# ESP_ILI9341_V3.net
KiCad netlist of a schematic drawn in EAGLE
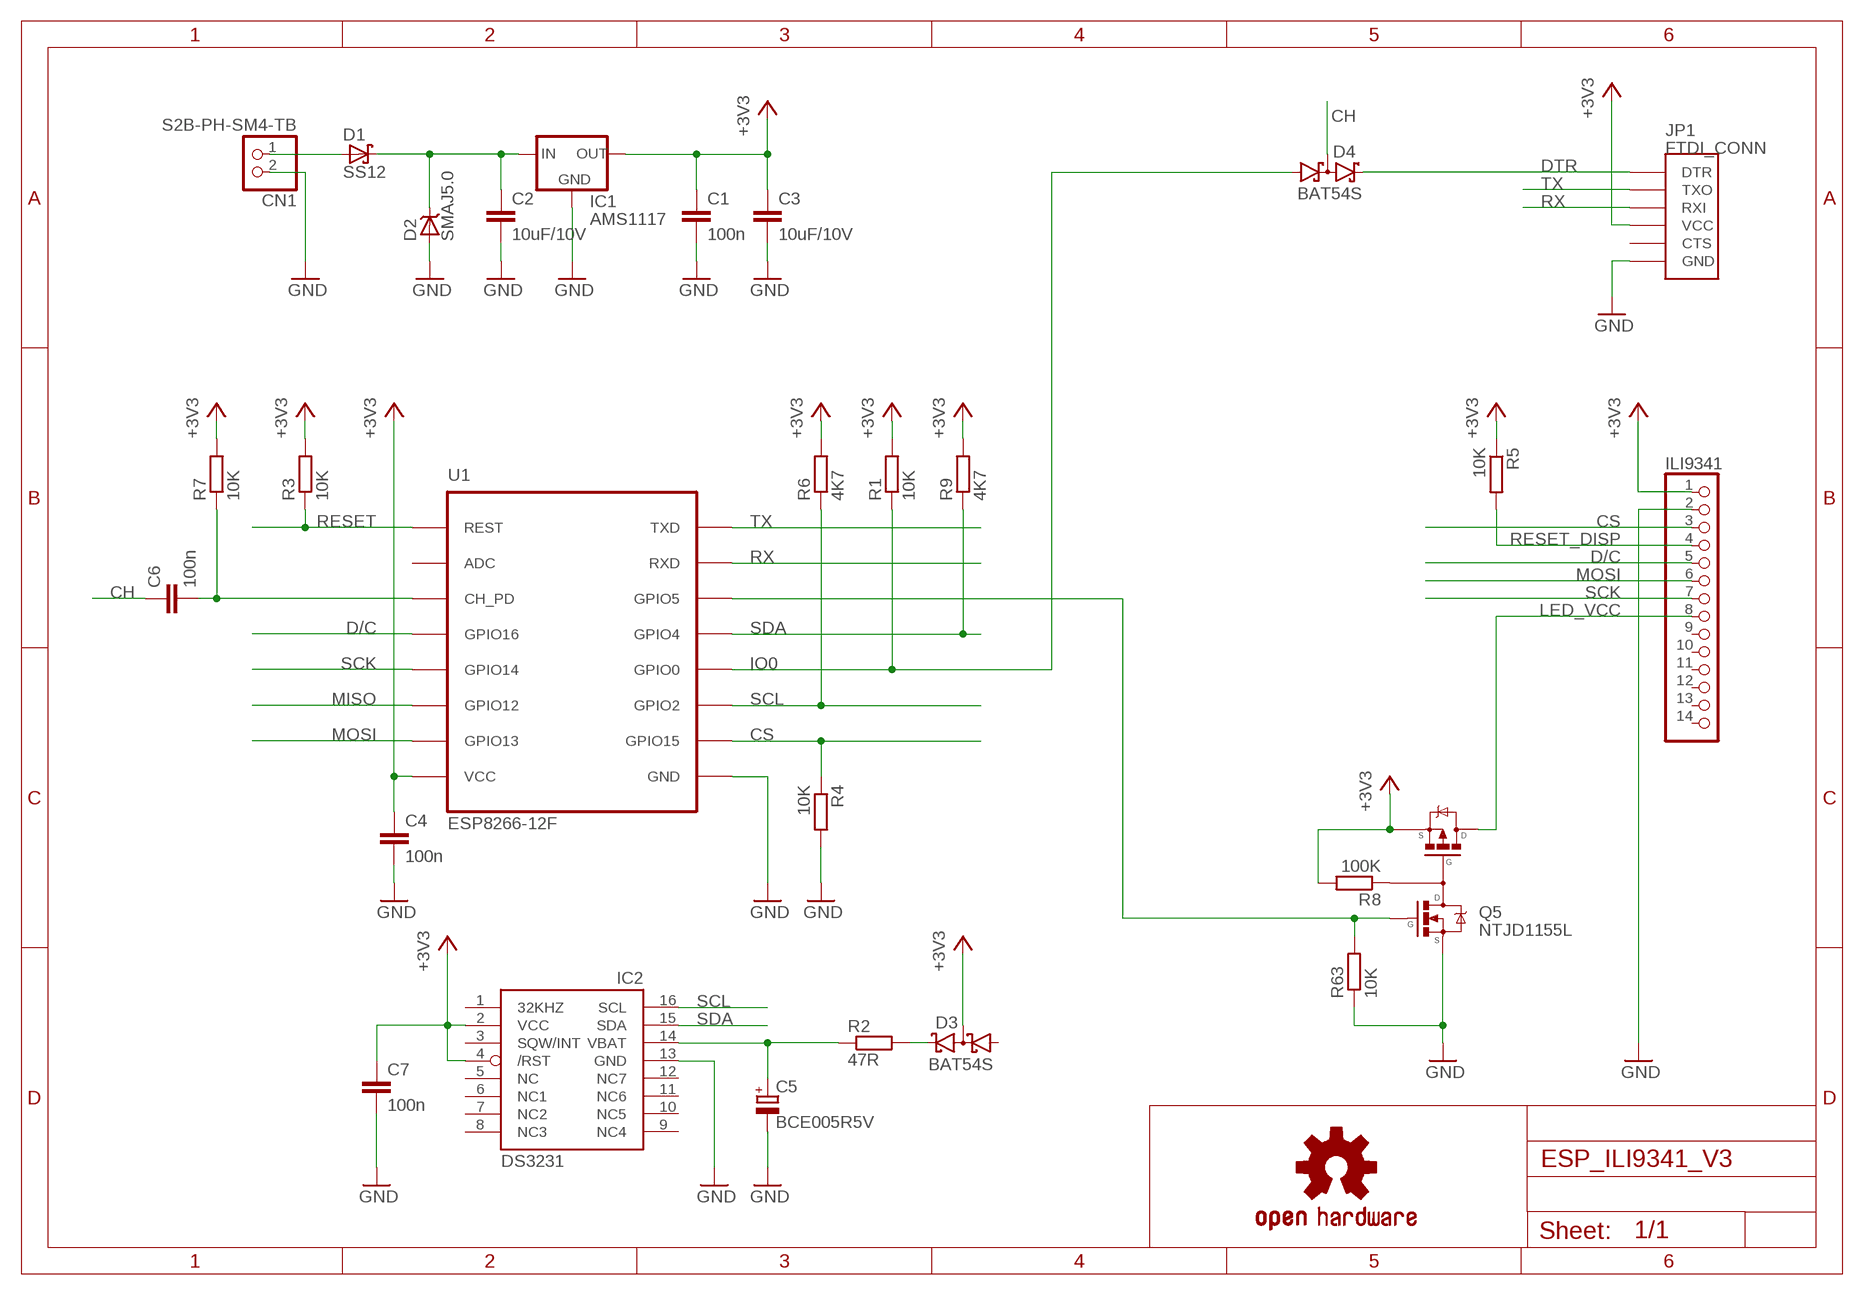
[diagram p0: schematic, sheet 1]

(export (version "E")
  (design (tool "Eeschema 10.0.6"))
  (components
    (comp (ref "C1")
      (value "100n")
      (footprint "eagle-import:C0805")
      (libsource (lib "eagle-import") (part "C-EUC0805"))
    )
    (comp (ref "C2")
      (value "10uF/10V")
      (footprint "eagle-import:C0805")
      (libsource (lib "eagle-import") (part "C-EUC0805"))
    )
    (comp (ref "C3")
      (value "10uF/10V")
      (footprint "eagle-import:C0805")
      (libsource (lib "eagle-import") (part "C-EUC0805"))
    )
    (comp (ref "C4")
      (value "100n")
      (footprint "eagle-import:C0805")
      (libsource (lib "eagle-import") (part "C-EUC0805"))
    )
    (comp (ref "C5")
      (value "BCE005R5V")
      (footprint "eagle-import:BCE")
      (libsource (lib "eagle-import") (part "BCE?V005R5"))
    )
    (comp (ref "C6")
      (value "100n")
      (footprint "eagle-import:C0805")
      (libsource (lib "eagle-import") (part "C-EUC0805"))
    )
    (comp (ref "C7")
      (value "100n")
      (footprint "eagle-import:C0805")
      (libsource (lib "eagle-import") (part "C-EUC0805"))
    )
    (comp (ref "CN1")
      (value "S2B-PH-SM4-TB")
      (footprint "eagle-import:JST-PH-2-SMT-RA")
      (libsource (lib "eagle-import") (part "JST_2PIN-SMT-RA"))
    )
    (comp (ref "D1")
      (value "SS12")
      (footprint "eagle-import:DO214AC")
      (libsource (lib "eagle-import") (part "SS?12"))
    )
    (comp (ref "D2")
      (value "SMAJ5.0")
      (footprint "eagle-import:DO214AC")
      (libsource (lib "eagle-import") (part "SM?JA5.0"))
    )
    (comp (ref "D3")
      (value "BAT54S")
      (footprint "eagle-import:SOT23")
      (libsource (lib "eagle-import") (part "BAT54S"))
    )
    (comp (ref "D4")
      (value "BAT54S")
      (footprint "eagle-import:SOT23")
      (libsource (lib "eagle-import") (part "BAT54S"))
    )
    (comp (ref "IC1")
      (value "AMS1117")
      (footprint "eagle-import:SOT223")
      (libsource (lib "eagle-import") (part "LM1117-3.3"))
    )
    (comp (ref "IC2")
      (value "DS3231/SO")
      (footprint "eagle-import:SO16W")
      (libsource (lib "eagle-import") (part "DS3231/SO"))
    )
    (comp (ref "ILI9341")
      (value "PINHD-1X14")
      (footprint "eagle-import:1X14")
      (libsource (lib "eagle-import") (part "PINHD-1X14"))
    )
    (comp (ref "JP1")
      (value "FTDI_CONN")
      (footprint "eagle-import:FTDI")
      (libsource (lib "eagle-import") (part "FTDI_CONN"))
    )
    (comp (ref "LOGO1")
      (value "OSHW-LOGOM-COPPER")
      (footprint "eagle-import:OSHW-LOGO-M_COPPER")
      (libsource (lib "eagle-import") (part "OSHW-LOGOM-COPPER"))
    )
    (comp (ref "Q5")
      (value "NTJD1155L")
      (footprint "eagle-import:SOT363")
      (libsource (lib "eagle-import") (part "NTJD1155L"))
    )
    (comp (ref "R1")
      (value "10K")
      (footprint "eagle-import:R0805")
      (libsource (lib "eagle-import") (part "R-EU_R0805"))
    )
    (comp (ref "R2")
      (value "47R")
      (footprint "eagle-import:R1206")
      (libsource (lib "eagle-import") (part "rcl_334_R-EU_R1206"))
    )
    (comp (ref "R3")
      (value "10K")
      (footprint "eagle-import:R0805")
      (libsource (lib "eagle-import") (part "R-EU_R0805"))
    )
    (comp (ref "R4")
      (value "10K")
      (footprint "eagle-import:R0805")
      (libsource (lib "eagle-import") (part "R-EU_R0805"))
    )
    (comp (ref "R5")
      (value "10K")
      (footprint "eagle-import:R0805")
      (libsource (lib "eagle-import") (part "R-EU_R0805"))
    )
    (comp (ref "R6")
      (value "4K7")
      (footprint "eagle-import:R0805")
      (libsource (lib "eagle-import") (part "R-EU_R0805"))
    )
    (comp (ref "R7")
      (value "10K")
      (footprint "eagle-import:R0805")
      (libsource (lib "eagle-import") (part "R-EU_R0805"))
    )
    (comp (ref "R8")
      (value "100K")
      (footprint "eagle-import:R0805")
      (libsource (lib "eagle-import") (part "R-EU_R0805"))
    )
    (comp (ref "R9")
      (value "4K7")
      (footprint "eagle-import:R0805")
      (libsource (lib "eagle-import") (part "R-EU_R0805"))
    )
    (comp (ref "R63")
      (value "10K")
      (footprint "eagle-import:R0805")
      (libsource (lib "eagle-import") (part "rcl_334_R-EU_R0805"))
    )
    (comp (ref "U1")
      (value "ESP8266-12F")
      (footprint "eagle-import:ESP-12")
      (libsource (lib "eagle-import") (part "ESP8266-12S"))
    )
  )
  (nets
    (net (code "1") (name "+3V3") (class "Default")
      (node (ref "C1") (pin "1") (pinfunction "1_1") (pintype "passive"))
      (node (ref "C3") (pin "1") (pinfunction "1_1") (pintype "passive"))
      (node (ref "C4") (pin "1") (pinfunction "1_1") (pintype "passive"))
      (node (ref "C7") (pin "1") (pinfunction "1_1") (pintype "passive"))
      (node (ref "D3") (pin "3") (pinfunction "C1A2_3") (pintype "passive"))
      (node (ref "IC1") (pin "2") (pinfunction "OUT_2") (pintype "output"))
      (node (ref "IC1") (pin "4") (pinfunction "OUT_4") (pintype "output"))
      (node (ref "IC2") (pin "2") (pinfunction "VCC_2") (pintype "power_in"))
      (node (ref "IC2") (pin "4") (pinfunction "/RST_4") (pintype "passive"))
      (node (ref "ILI9341") (pin "1") (pinfunction "1_1") (pintype "passive"))
      (node (ref "JP1") (pin "P$4") (pinfunction "VCC_P$4") (pintype "bidirectional"))
      (node (ref "Q5") (pin "4") (pinfunction "S2_4") (pintype "passive"))
      (node (ref "R1") (pin "2") (pinfunction "2_2") (pintype "passive"))
      (node (ref "R3") (pin "2") (pinfunction "2_2") (pintype "passive"))
      (node (ref "R5") (pin "1") (pinfunction "1_1") (pintype "passive"))
      (node (ref "R6") (pin "2") (pinfunction "2_2") (pintype "passive"))
      (node (ref "R7") (pin "2") (pinfunction "2_2") (pintype "passive"))
      (node (ref "R8") (pin "2") (pinfunction "2_2") (pintype "passive"))
      (node (ref "R9") (pin "2") (pinfunction "2_2") (pintype "passive"))
      (node (ref "U1") (pin "VCC") (pinfunction "VCC_VCC") (pintype "power_in"))
    )
    (net (code "2") (name "/CH") (class "Default")
      (node (ref "C6") (pin "1") (pinfunction "1_1") (pintype "passive"))
      (node (ref "D4") (pin "3") (pinfunction "C1A2_3") (pintype "passive"))
    )
    (net (code "3") (name "/CS") (class "Default")
      (node (ref "ILI9341") (pin "3") (pinfunction "3_3") (pintype "passive"))
      (node (ref "R4") (pin "1") (pinfunction "1_1") (pintype "passive"))
      (node (ref "U1") (pin "GPIO15") (pinfunction "GPIO15_GPIO15") (pintype "bidirectional"))
    )
    (net (code "4") (name "/DTR") (class "Default")
      (node (ref "D4") (pin "2") (pinfunction "C2_2") (pintype "passive"))
      (node (ref "JP1") (pin "P$1") (pinfunction "DTR_P$1") (pintype "bidirectional"))
    )
    (net (code "5") (name "/D{slash}C") (class "Default")
      (node (ref "ILI9341") (pin "5") (pinfunction "5_5") (pintype "passive"))
      (node (ref "U1") (pin "GPIO16") (pinfunction "GPIO16_GPIO16") (pintype "bidirectional"))
    )
    (net (code "6") (name "/IO0") (class "Default")
      (node (ref "D4") (pin "1") (pinfunction "A1_1") (pintype "passive"))
      (node (ref "R1") (pin "1") (pinfunction "1_1") (pintype "passive"))
      (node (ref "U1") (pin "GPIO0") (pinfunction "GPIO0_GPIO0") (pintype "bidirectional"))
    )
    (net (code "7") (name "/LED_VCC") (class "Default")
      (node (ref "ILI9341") (pin "8") (pinfunction "8_8") (pintype "passive"))
      (node (ref "Q5") (pin "2") (pinfunction "D2_2") (pintype "passive"))
      (node (ref "Q5") (pin "3") (pinfunction "D2_3") (pintype "passive"))
    )
    (net (code "8") (name "/MISO") (class "Default")
      (node (ref "U1") (pin "GPIO12") (pinfunction "GPIO12_GPIO12") (pintype "bidirectional"))
    )
    (net (code "9") (name "/MOSI") (class "Default")
      (node (ref "ILI9341") (pin "6") (pinfunction "6_6") (pintype "passive"))
      (node (ref "U1") (pin "GPIO13") (pinfunction "GPIO13_GPIO13") (pintype "bidirectional"))
    )
    (net (code "10") (name "/RESET") (class "Default")
      (node (ref "R3") (pin "1") (pinfunction "1_1") (pintype "passive"))
      (node (ref "U1") (pin "REST") (pinfunction "REST_REST") (pintype "bidirectional"))
    )
    (net (code "11") (name "/RESET_DISP") (class "Default")
      (node (ref "ILI9341") (pin "4") (pinfunction "4_4") (pintype "passive"))
      (node (ref "R5") (pin "2") (pinfunction "2_2") (pintype "passive"))
    )
    (net (code "12") (name "/RX") (class "Default")
      (node (ref "JP1") (pin "P$3") (pinfunction "RXI_P$3") (pintype "bidirectional"))
      (node (ref "U1") (pin "RXD") (pinfunction "RXD_RXD") (pintype "bidirectional"))
    )
    (net (code "13") (name "/SCK") (class "Default")
      (node (ref "ILI9341") (pin "7") (pinfunction "7_7") (pintype "passive"))
      (node (ref "U1") (pin "GPIO14") (pinfunction "GPIO14_GPIO14") (pintype "bidirectional"))
    )
    (net (code "14") (name "/SCL") (class "Default")
      (node (ref "IC2") (pin "16") (pinfunction "SCL_16") (pintype "bidirectional"))
      (node (ref "R6") (pin "1") (pinfunction "1_1") (pintype "passive"))
      (node (ref "U1") (pin "GPIO2") (pinfunction "GPIO2_GPIO2") (pintype "bidirectional"))
    )
    (net (code "15") (name "/SDA") (class "Default")
      (node (ref "IC2") (pin "15") (pinfunction "SDA_15") (pintype "bidirectional"))
      (node (ref "R9") (pin "1") (pinfunction "1_1") (pintype "passive"))
      (node (ref "U1") (pin "GPIO4") (pinfunction "GPIO4_GPIO4") (pintype "bidirectional"))
    )
    (net (code "16") (name "/TX") (class "Default")
      (node (ref "JP1") (pin "P$2") (pinfunction "TXO_P$2") (pintype "bidirectional"))
      (node (ref "U1") (pin "TXD") (pinfunction "TXD_TXD") (pintype "bidirectional"))
    )
    (net (code "17") (name "GND") (class "Default")
      (node (ref "C1") (pin "2") (pinfunction "2_2") (pintype "passive"))
      (node (ref "C2") (pin "2") (pinfunction "2_2") (pintype "passive"))
      (node (ref "C3") (pin "2") (pinfunction "2_2") (pintype "passive"))
      (node (ref "C4") (pin "2") (pinfunction "2_2") (pintype "passive"))
      (node (ref "C5") (pin "-") (pinfunction "-_-") (pintype "passive"))
      (node (ref "C7") (pin "2") (pinfunction "2_2") (pintype "passive"))
      (node (ref "CN1") (pin "2") (pinfunction "1_2") (pintype "passive"))
      (node (ref "D2") (pin "A") (pinfunction "A_A") (pintype "passive"))
      (node (ref "IC1") (pin "1") (pinfunction "GND_1") (pintype "input"))
      (node (ref "IC2") (pin "13") (pinfunction "GND_13") (pintype "power_in"))
      (node (ref "ILI9341") (pin "2") (pinfunction "2_2") (pintype "passive"))
      (node (ref "JP1") (pin "P$6") (pinfunction "GND_P$6") (pintype "bidirectional"))
      (node (ref "Q5") (pin "1") (pinfunction "S1_1") (pintype "passive"))
      (node (ref "R4") (pin "2") (pinfunction "2_2") (pintype "passive"))
      (node (ref "R63") (pin "1") (pinfunction "1_1") (pintype "passive"))
      (node (ref "U1") (pin "GND") (pinfunction "GND_GND") (pintype "power_in"))
    )
    (net (code "18") (name "Net-(C6-Pad2)") (class "Default")
      (node (ref "C6") (pin "2") (pinfunction "2_2") (pintype "passive"))
      (node (ref "R7") (pin "1") (pinfunction "1_1") (pintype "passive"))
      (node (ref "U1") (pin "CH_PD") (pinfunction "CH_PD_CH_PD") (pintype "power_in"))
    )
    (net (code "19") (name "Net-(CN1-2)") (class "Default")
      (node (ref "CN1") (pin "1") (pinfunction "2_1") (pintype "passive"))
      (node (ref "D1") (pin "A") (pinfunction "A_A") (pintype "passive"))
    )
    (net (code "20") (name "Net-(D3-C2)") (class "Default")
      (node (ref "D3") (pin "2") (pinfunction "C2_2") (pintype "passive"))
      (node (ref "R2") (pin "2") (pinfunction "2_2") (pintype "passive"))
    )
    (net (code "21") (name "Net-(IC1-IN)") (class "Default")
      (node (ref "C2") (pin "1") (pinfunction "1_1") (pintype "passive"))
      (node (ref "D1") (pin "C") (pinfunction "C_C") (pintype "passive"))
      (node (ref "D2") (pin "C") (pinfunction "C_C") (pintype "passive"))
      (node (ref "IC1") (pin "3") (pinfunction "IN_3") (pintype "input"))
    )
    (net (code "22") (name "Net-(IC2-VBAT)") (class "Default")
      (node (ref "C5") (pin "+") (pinfunction "+_+") (pintype "passive"))
      (node (ref "IC2") (pin "14") (pinfunction "VBAT_14") (pintype "power_in"))
      (node (ref "R2") (pin "1") (pinfunction "1_1") (pintype "passive"))
    )
    (net (code "23") (name "Net-(Q5-D1{slash}G2)") (class "Default")
      (node (ref "Q5") (pin "6") (pinfunction "D1/G2_6") (pintype "passive"))
      (node (ref "R8") (pin "1") (pinfunction "1_1") (pintype "passive"))
    )
    (net (code "24") (name "Net-(Q5-G1)") (class "Default")
      (node (ref "Q5") (pin "5") (pinfunction "G1_5") (pintype "passive"))
      (node (ref "R63") (pin "2") (pinfunction "2_2") (pintype "passive"))
      (node (ref "U1") (pin "GPIO5") (pinfunction "GPIO5_GPIO5") (pintype "bidirectional"))
    )
    (net (code "25") (name "unconnected-(D3-A1-Pad1)") (class "Default")
      (node (ref "D3") (pin "1") (pinfunction "A1_1") (pintype "passive"))
    )
    (net (code "26") (name "unconnected-(IC2-32KHZ-Pad1)") (class "Default")
      (node (ref "IC2") (pin "1") (pinfunction "32KHZ_1") (pintype "output"))
    )
    (net (code "27") (name "unconnected-(IC2-NC-Pad5)") (class "Default")
      (node (ref "IC2") (pin "5") (pinfunction "NC_5") (pintype "no_connect"))
    )
    (net (code "28") (name "unconnected-(IC2-NC1-Pad6)") (class "Default")
      (node (ref "IC2") (pin "6") (pinfunction "NC1_6") (pintype "no_connect"))
    )
    (net (code "29") (name "unconnected-(IC2-NC2-Pad7)") (class "Default")
      (node (ref "IC2") (pin "7") (pinfunction "NC2_7") (pintype "no_connect"))
    )
    (net (code "30") (name "unconnected-(IC2-NC3-Pad8)") (class "Default")
      (node (ref "IC2") (pin "8") (pinfunction "NC3_8") (pintype "no_connect"))
    )
    (net (code "31") (name "unconnected-(IC2-NC4-Pad9)") (class "Default")
      (node (ref "IC2") (pin "9") (pinfunction "NC4_9") (pintype "no_connect"))
    )
    (net (code "32") (name "unconnected-(IC2-NC5-Pad10)") (class "Default")
      (node (ref "IC2") (pin "10") (pinfunction "NC5_10") (pintype "no_connect"))
    )
    (net (code "33") (name "unconnected-(IC2-NC6-Pad11)") (class "Default")
      (node (ref "IC2") (pin "11") (pinfunction "NC6_11") (pintype "no_connect"))
    )
    (net (code "34") (name "unconnected-(IC2-NC7-Pad12)") (class "Default")
      (node (ref "IC2") (pin "12") (pinfunction "NC7_12") (pintype "no_connect"))
    )
    (net (code "35") (name "unconnected-(IC2-SQW{slash}INT-Pad3)") (class "Default")
      (node (ref "IC2") (pin "3") (pinfunction "SQW/INT_3") (pintype "output"))
    )
    (net (code "36") (name "unconnected-(ILI9341-Pad9)") (class "Default")
      (node (ref "ILI9341") (pin "9") (pinfunction "9_9") (pintype "passive"))
    )
    (net (code "37") (name "unconnected-(ILI9341-Pad10)") (class "Default")
      (node (ref "ILI9341") (pin "10") (pinfunction "10_10") (pintype "passive"))
    )
    (net (code "38") (name "unconnected-(ILI9341-Pad11)") (class "Default")
      (node (ref "ILI9341") (pin "11") (pinfunction "11_11") (pintype "passive"))
    )
    (net (code "39") (name "unconnected-(ILI9341-Pad12)") (class "Default")
      (node (ref "ILI9341") (pin "12") (pinfunction "12_12") (pintype "passive"))
    )
    (net (code "40") (name "unconnected-(ILI9341-Pad13)") (class "Default")
      (node (ref "ILI9341") (pin "13") (pinfunction "13_13") (pintype "passive"))
    )
    (net (code "41") (name "unconnected-(ILI9341-Pad14)") (class "Default")
      (node (ref "ILI9341") (pin "14") (pinfunction "14_14") (pintype "passive"))
    )
    (net (code "42") (name "unconnected-(JP1-CTS-PadP$5)") (class "Default")
      (node (ref "JP1") (pin "P$5") (pinfunction "CTS_P$5") (pintype "bidirectional"))
    )
    (net (code "43") (name "unconnected-(U1-PadADC)") (class "Default")
      (node (ref "U1") (pin "ADC") (pinfunction "ADC_ADC") (pintype "bidirectional"))
    )
  )
)
